# Input_Cover_Breakout.net
KiCad netlist of a schematic drawn in Altium Designer
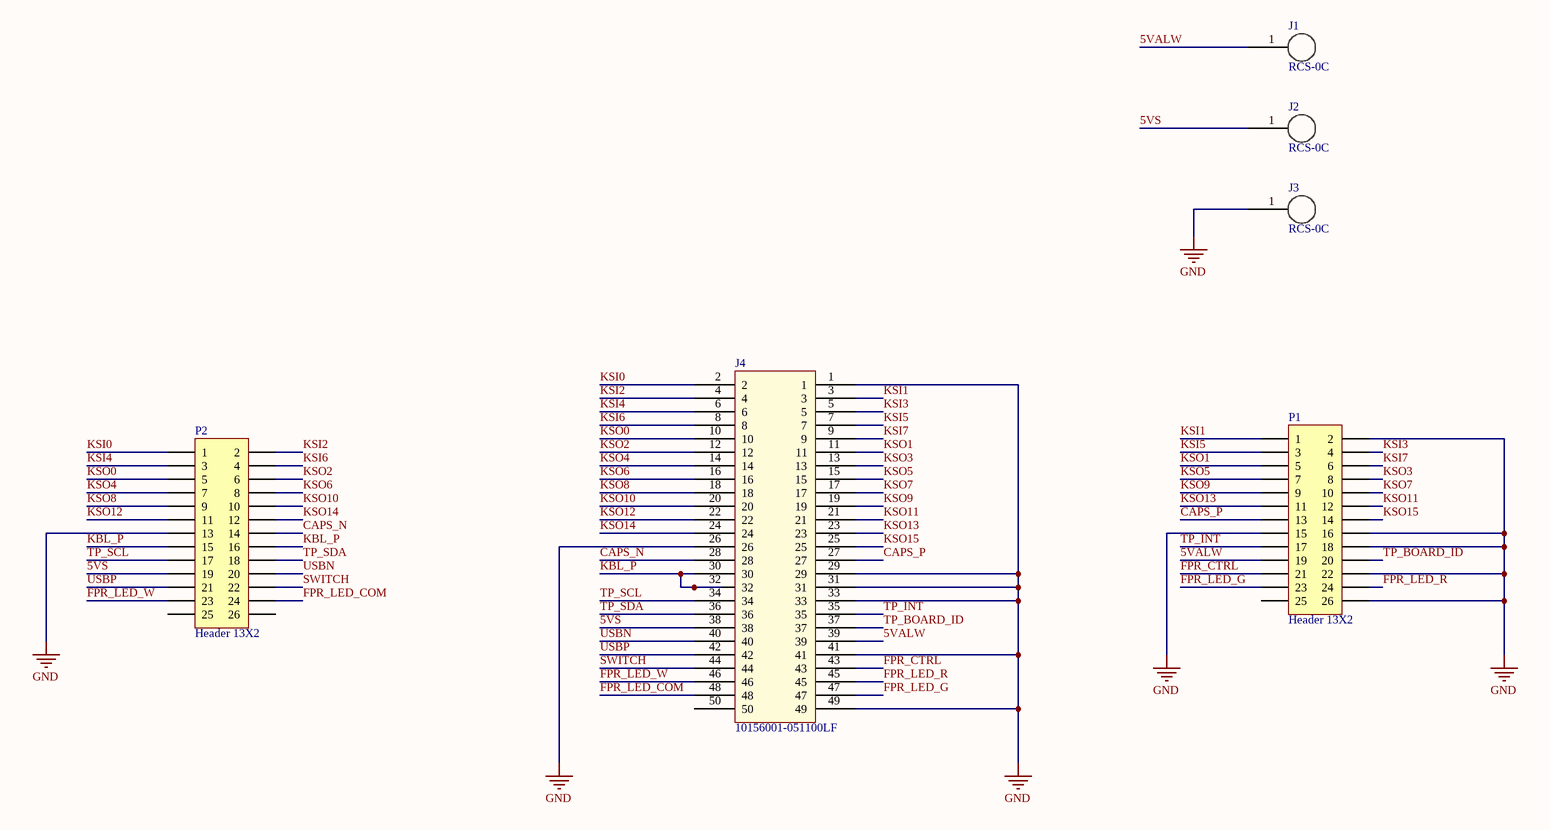
[diagram p0: Input Cover Breakout.SchDoc]

(export (version "E")
  (design (tool "Eeschema 10.0.6"))
  (components
    (comp (ref "J1") (value "RCS-0C") (footprint "RCS-0C") (libsource (lib "KBuchka-IntLib") (part "RCS-0C")))
    (comp (ref "J2") (value "RCS-0C") (footprint "RCS-0C") (libsource (lib "KBuchka-IntLib") (part "RCS-0C")))
    (comp (ref "J3") (value "RCS-0C") (footprint "RCS-0C") (libsource (lib "KBuchka-IntLib") (part "RCS-0C")))
    (comp (ref "J4")
      (value "10156001-051100LF")
      (footprint "10156001-051100LF")
      (libsource (lib "KBuchka-IntLib") (part "10156001-051100LF"))
    )
    (comp (ref "P1")
      (value "Header 13X2")
      (footprint "HDR2X13")
      (description "Header, 13-Pin, Dual row")
      (fields (field (name "PUBLISHER") "Altium Limited"))
      (libsource (lib "Miscellaneous Connectors") (part "Header 13X2"))
    )
    (comp (ref "P2")
      (value "Header 13X2")
      (footprint "HDR2X13")
      (description "Header, 13-Pin, Dual row")
      (fields (field (name "PUBLISHER") "Altium Limited"))
      (libsource (lib "Miscellaneous Connectors") (part "Header 13X2"))
    )
  )
  (nets
    (net (code "1") (name "/5VALW") (class "Default")
      (node (ref "J1") (pin "1") (pinfunction "1_1") (pintype "passive"))
      (node (ref "J4") (pin "39") (pinfunction "39_39") (pintype "passive"))
      (node (ref "P1") (pin "19") (pinfunction "19_19") (pintype "passive"))
    )
    (net (code "2") (name "/5VS") (class "Default")
      (node (ref "J2") (pin "1") (pinfunction "1_1") (pintype "passive"))
      (node (ref "J4") (pin "38") (pinfunction "38_38") (pintype "passive"))
      (node (ref "P2") (pin "19") (pinfunction "19_19") (pintype "passive"))
    )
    (net (code "3") (name "/CAPS_N") (class "Default")
      (node (ref "J4") (pin "28") (pinfunction "28_28") (pintype "passive"))
      (node (ref "P2") (pin "14") (pinfunction "14_14") (pintype "passive"))
    )
    (net (code "4") (name "/CAPS_P") (class "Default")
      (node (ref "J4") (pin "27") (pinfunction "27_27") (pintype "passive"))
      (node (ref "P1") (pin "13") (pinfunction "13_13") (pintype "passive"))
    )
    (net (code "5") (name "/FPR_CTRL") (class "Default")
      (node (ref "J4") (pin "43") (pinfunction "43_43") (pintype "passive"))
      (node (ref "P1") (pin "21") (pinfunction "21_21") (pintype "passive"))
    )
    (net (code "6") (name "/FPR_LED_COM") (class "Default")
      (node (ref "J4") (pin "48") (pinfunction "48_48") (pintype "passive"))
      (node (ref "P2") (pin "24") (pinfunction "24_24") (pintype "passive"))
    )
    (net (code "7") (name "/FPR_LED_G") (class "Default")
      (node (ref "J4") (pin "47") (pinfunction "47_47") (pintype "passive"))
      (node (ref "P1") (pin "23") (pinfunction "23_23") (pintype "passive"))
    )
    (net (code "8") (name "/FPR_LED_R") (class "Default")
      (node (ref "J4") (pin "45") (pinfunction "45_45") (pintype "passive"))
      (node (ref "P1") (pin "24") (pinfunction "24_24") (pintype "passive"))
    )
    (net (code "9") (name "/FPR_LED_W") (class "Default")
      (node (ref "J4") (pin "46") (pinfunction "46_46") (pintype "passive"))
      (node (ref "P2") (pin "23") (pinfunction "23_23") (pintype "passive"))
    )
    (net (code "10") (name "/KBL_P") (class "Default")
      (node (ref "J4") (pin "30") (pinfunction "30_30") (pintype "passive"))
      (node (ref "J4") (pin "32") (pinfunction "32_32") (pintype "passive"))
      (node (ref "P2") (pin "15") (pinfunction "15_15") (pintype "passive"))
      (node (ref "P2") (pin "16") (pinfunction "16_16") (pintype "passive"))
    )
    (net (code "11") (name "/KSI0") (class "Default")
      (node (ref "J4") (pin "2") (pinfunction "2_2") (pintype "passive"))
      (node (ref "P2") (pin "1") (pinfunction "1_1") (pintype "passive"))
    )
    (net (code "12") (name "/KSI1") (class "Default")
      (node (ref "J4") (pin "3") (pinfunction "3_3") (pintype "passive"))
      (node (ref "P1") (pin "1") (pinfunction "1_1") (pintype "passive"))
    )
    (net (code "13") (name "/KSI2") (class "Default")
      (node (ref "J4") (pin "4") (pinfunction "4_4") (pintype "passive"))
      (node (ref "P2") (pin "2") (pinfunction "2_2") (pintype "passive"))
    )
    (net (code "14") (name "/KSI3") (class "Default")
      (node (ref "J4") (pin "5") (pinfunction "5_5") (pintype "passive"))
      (node (ref "P1") (pin "4") (pinfunction "4_4") (pintype "passive"))
    )
    (net (code "15") (name "/KSI4") (class "Default")
      (node (ref "J4") (pin "6") (pinfunction "6_6") (pintype "passive"))
      (node (ref "P2") (pin "3") (pinfunction "3_3") (pintype "passive"))
    )
    (net (code "16") (name "/KSI5") (class "Default")
      (node (ref "J4") (pin "7") (pinfunction "7_7") (pintype "passive"))
      (node (ref "P1") (pin "3") (pinfunction "3_3") (pintype "passive"))
    )
    (net (code "17") (name "/KSI6") (class "Default")
      (node (ref "J4") (pin "8") (pinfunction "8_8") (pintype "passive"))
      (node (ref "P2") (pin "4") (pinfunction "4_4") (pintype "passive"))
    )
    (net (code "18") (name "/KSI7") (class "Default")
      (node (ref "J4") (pin "9") (pinfunction "9_9") (pintype "passive"))
      (node (ref "P1") (pin "6") (pinfunction "6_6") (pintype "passive"))
    )
    (net (code "19") (name "/KSO0") (class "Default")
      (node (ref "J4") (pin "10") (pinfunction "10_10") (pintype "passive"))
      (node (ref "P2") (pin "5") (pinfunction "5_5") (pintype "passive"))
    )
    (net (code "20") (name "/KSO1") (class "Default")
      (node (ref "J4") (pin "11") (pinfunction "11_11") (pintype "passive"))
      (node (ref "P1") (pin "5") (pinfunction "5_5") (pintype "passive"))
    )
    (net (code "21") (name "/KSO2") (class "Default")
      (node (ref "J4") (pin "12") (pinfunction "12_12") (pintype "passive"))
      (node (ref "P2") (pin "6") (pinfunction "6_6") (pintype "passive"))
    )
    (net (code "22") (name "/KSO3") (class "Default")
      (node (ref "J4") (pin "13") (pinfunction "13_13") (pintype "passive"))
      (node (ref "P1") (pin "8") (pinfunction "8_8") (pintype "passive"))
    )
    (net (code "23") (name "/KSO4") (class "Default")
      (node (ref "J4") (pin "14") (pinfunction "14_14") (pintype "passive"))
      (node (ref "P2") (pin "7") (pinfunction "7_7") (pintype "passive"))
    )
    (net (code "24") (name "/KSO5") (class "Default")
      (node (ref "J4") (pin "15") (pinfunction "15_15") (pintype "passive"))
      (node (ref "P1") (pin "7") (pinfunction "7_7") (pintype "passive"))
    )
    (net (code "25") (name "/KSO6") (class "Default")
      (node (ref "J4") (pin "16") (pinfunction "16_16") (pintype "passive"))
      (node (ref "P2") (pin "8") (pinfunction "8_8") (pintype "passive"))
    )
    (net (code "26") (name "/KSO7") (class "Default")
      (node (ref "J4") (pin "17") (pinfunction "17_17") (pintype "passive"))
      (node (ref "P1") (pin "10") (pinfunction "10_10") (pintype "passive"))
    )
    (net (code "27") (name "/KSO8") (class "Default")
      (node (ref "J4") (pin "18") (pinfunction "18_18") (pintype "passive"))
      (node (ref "P2") (pin "9") (pinfunction "9_9") (pintype "passive"))
    )
    (net (code "28") (name "/KSO9") (class "Default")
      (node (ref "J4") (pin "19") (pinfunction "19_19") (pintype "passive"))
      (node (ref "P1") (pin "9") (pinfunction "9_9") (pintype "passive"))
    )
    (net (code "29") (name "/KSO10") (class "Default")
      (node (ref "J4") (pin "20") (pinfunction "20_20") (pintype "passive"))
      (node (ref "P2") (pin "10") (pinfunction "10_10") (pintype "passive"))
    )
    (net (code "30") (name "/KSO11") (class "Default")
      (node (ref "J4") (pin "21") (pinfunction "21_21") (pintype "passive"))
      (node (ref "P1") (pin "12") (pinfunction "12_12") (pintype "passive"))
    )
    (net (code "31") (name "/KSO12") (class "Default")
      (node (ref "J4") (pin "22") (pinfunction "22_22") (pintype "passive"))
      (node (ref "P2") (pin "11") (pinfunction "11_11") (pintype "passive"))
    )
    (net (code "32") (name "/KSO13") (class "Default")
      (node (ref "J4") (pin "23") (pinfunction "23_23") (pintype "passive"))
      (node (ref "P1") (pin "11") (pinfunction "11_11") (pintype "passive"))
    )
    (net (code "33") (name "/KSO14") (class "Default")
      (node (ref "J4") (pin "24") (pinfunction "24_24") (pintype "passive"))
      (node (ref "P2") (pin "12") (pinfunction "12_12") (pintype "passive"))
    )
    (net (code "34") (name "/KSO15") (class "Default")
      (node (ref "J4") (pin "25") (pinfunction "25_25") (pintype "passive"))
      (node (ref "P1") (pin "14") (pinfunction "14_14") (pintype "passive"))
    )
    (net (code "35") (name "/SWITCH") (class "Default")
      (node (ref "J4") (pin "44") (pinfunction "44_44") (pintype "passive"))
      (node (ref "P2") (pin "22") (pinfunction "22_22") (pintype "passive"))
    )
    (net (code "36") (name "/TP_BOARD_ID") (class "Default")
      (node (ref "J4") (pin "37") (pinfunction "37_37") (pintype "passive"))
      (node (ref "P1") (pin "20") (pinfunction "20_20") (pintype "passive"))
    )
    (net (code "37") (name "/TP_INT") (class "Default")
      (node (ref "J4") (pin "35") (pinfunction "35_35") (pintype "passive"))
      (node (ref "P1") (pin "17") (pinfunction "17_17") (pintype "passive"))
    )
    (net (code "38") (name "/TP_SCL") (class "Default")
      (node (ref "J4") (pin "34") (pinfunction "34_34") (pintype "passive"))
      (node (ref "P2") (pin "17") (pinfunction "17_17") (pintype "passive"))
    )
    (net (code "39") (name "/TP_SDA") (class "Default")
      (node (ref "J4") (pin "36") (pinfunction "36_36") (pintype "passive"))
      (node (ref "P2") (pin "18") (pinfunction "18_18") (pintype "passive"))
    )
    (net (code "40") (name "/USBN") (class "Default")
      (node (ref "J4") (pin "40") (pinfunction "40_40") (pintype "passive"))
      (node (ref "P2") (pin "20") (pinfunction "20_20") (pintype "passive"))
    )
    (net (code "41") (name "/USBP") (class "Default")
      (node (ref "J4") (pin "42") (pinfunction "42_42") (pintype "passive"))
      (node (ref "P2") (pin "21") (pinfunction "21_21") (pintype "passive"))
    )
    (net (code "42") (name "GND") (class "Default")
      (node (ref "J3") (pin "1") (pinfunction "1_1") (pintype "passive"))
      (node (ref "J4") (pin "1") (pinfunction "1_1") (pintype "passive"))
      (node (ref "J4") (pin "26") (pinfunction "26_26") (pintype "passive"))
      (node (ref "J4") (pin "29") (pinfunction "29_29") (pintype "passive"))
      (node (ref "J4") (pin "31") (pinfunction "31_31") (pintype "passive"))
      (node (ref "J4") (pin "33") (pinfunction "33_33") (pintype "passive"))
      (node (ref "J4") (pin "41") (pinfunction "41_41") (pintype "passive"))
      (node (ref "J4") (pin "49") (pinfunction "49_49") (pintype "passive"))
      (node (ref "P1") (pin "15") (pinfunction "15_15") (pintype "passive"))
      (node (ref "P1") (pin "16") (pinfunction "16_16") (pintype "passive"))
      (node (ref "P1") (pin "18") (pinfunction "18_18") (pintype "passive"))
      (node (ref "P1") (pin "2") (pinfunction "2_2") (pintype "passive"))
      (node (ref "P1") (pin "22") (pinfunction "22_22") (pintype "passive"))
      (node (ref "P1") (pin "26") (pinfunction "26_26") (pintype "passive"))
      (node (ref "P2") (pin "13") (pinfunction "13_13") (pintype "passive"))
    )
    (net (code "43") (name "unconnected-(J4-Pad50)") (class "Default")
      (node (ref "J4") (pin "50") (pinfunction "50_50") (pintype "passive"))
    )
    (net (code "44") (name "unconnected-(P1-Pad25)") (class "Default")
      (node (ref "P1") (pin "25") (pinfunction "25_25") (pintype "passive"))
    )
    (net (code "45") (name "unconnected-(P2-Pad25)") (class "Default")
      (node (ref "P2") (pin "25") (pinfunction "25_25") (pintype "passive"))
    )
    (net (code "46") (name "unconnected-(P2-Pad26)") (class "Default")
      (node (ref "P2") (pin "26") (pinfunction "26_26") (pintype "passive"))
    )
  )
)
